# arduino_Uno_Rev3-02-TH.net
KiCad netlist of a schematic drawn in EAGLE
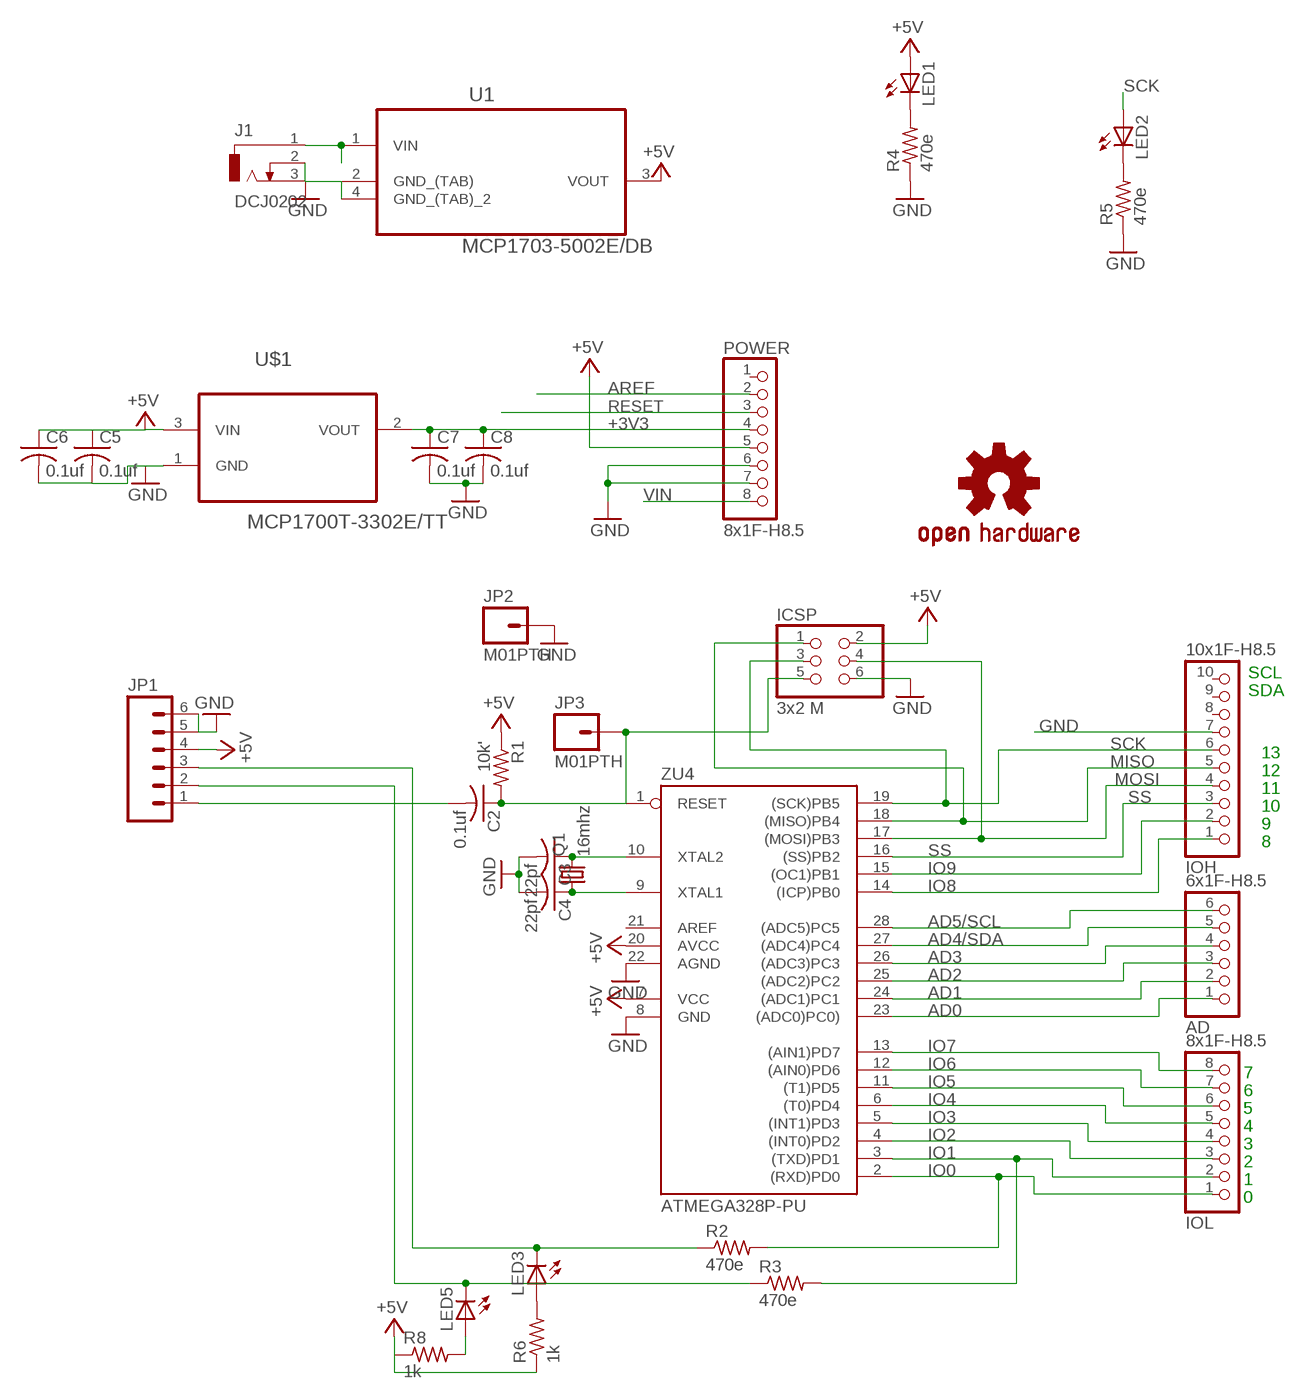
[diagram p0: schematic, sheet 1]

(export (version "E")
  (design (tool "Eeschema 10.0.6"))
  (components
    (comp (ref "AD")
      (value "6x1F-H8.5")
      (footprint "eagle-import:1X06")
      (libsource (lib "eagle-import") (part "PINHD-1X6"))
    )
    (comp (ref "C2")
      (value "0.1uf")
      (footprint "eagle-import:C0603")
      (libsource (lib "eagle-import") (part "C-USC0603"))
    )
    (comp (ref "C3")
      (value "22pf")
      (footprint "eagle-import:C1206")
      (libsource (lib "eagle-import") (part "C-USC1206"))
    )
    (comp (ref "C4")
      (value "22pf")
      (footprint "eagle-import:C1206")
      (libsource (lib "eagle-import") (part "C-USC1206"))
    )
    (comp (ref "C5")
      (value "0.1uf")
      (footprint "eagle-import:C0603")
      (libsource (lib "eagle-import") (part "C-USC0603"))
    )
    (comp (ref "C6")
      (value "0.1uf")
      (footprint "eagle-import:C0603")
      (libsource (lib "eagle-import") (part "C-USC0603"))
    )
    (comp (ref "C7")
      (value "0.1uf")
      (footprint "eagle-import:C0603")
      (libsource (lib "eagle-import") (part "C-USC0603"))
    )
    (comp (ref "C8")
      (value "0.1uf")
      (footprint "eagle-import:C0603")
      (libsource (lib "eagle-import") (part "C-USC0603"))
    )
    (comp (ref "ICSP")
      (value "3x2 M")
      (footprint "eagle-import:2X03")
      (libsource (lib "eagle-import") (part "PINHD-2X3"))
    )
    (comp (ref "IOH")
      (value "10x1F-H8.5")
      (footprint "eagle-import:1X10")
      (libsource (lib "eagle-import") (part "PINHD-1X10_ARD"))
    )
    (comp (ref "IOL")
      (value "8x1F-H8.5")
      (footprint "eagle-import:1X08")
      (libsource (lib "eagle-import") (part "PINHD-1X8"))
    )
    (comp (ref "J1")
      (value "DCJ0202")
      (footprint "eagle-import:DCJ0202")
      (libsource (lib "eagle-import") (part "DCJ0202"))
    )
    (comp (ref "JP1")
      (value "M06LONGPADS")
      (footprint "eagle-import:1X06_LONGPADS")
      (libsource (lib "eagle-import") (part "M06LONGPADS"))
    )
    (comp (ref "JP2")
      (value "M01PTH")
      (footprint "eagle-import:1X01")
      (libsource (lib "eagle-import") (part "M01PTH"))
    )
    (comp (ref "JP3")
      (value "M01PTH")
      (footprint "eagle-import:1X01")
      (libsource (lib "eagle-import") (part "M01PTH"))
    )
    (comp (ref "LED1")
      (value "LED3MM")
      (footprint "eagle-import:LED3MM")
      (libsource (lib "eagle-import") (part "LED3MM"))
    )
    (comp (ref "LED2")
      (value "LED3MM")
      (footprint "eagle-import:LED3MM")
      (libsource (lib "eagle-import") (part "LED3MM"))
    )
    (comp (ref "LED3")
      (value "LED3MM")
      (footprint "eagle-import:LED3MM")
      (libsource (lib "eagle-import") (part "LED3MM"))
    )
    (comp (ref "LED5")
      (value "LED3MM")
      (footprint "eagle-import:LED3MM")
      (libsource (lib "eagle-import") (part "LED3MM"))
    )
    (comp (ref "LOGO1")
      (value "OSHW-LOGOL")
      (footprint "eagle-import:OSHW-LOGO-L")
      (libsource (lib "eagle-import") (part "OSHW-LOGOL"))
    )
    (comp (ref "POWER")
      (value "8x1F-H8.5")
      (footprint "eagle-import:1X08")
      (libsource (lib "eagle-import") (part "PINHD-1X8"))
    )
    (comp (ref "Q1")
      (value "16mhz")
      (footprint "eagle-import:HC49_S")
      (libsource (lib "eagle-import") (part "CRYSTALHC49S"))
    )
    (comp (ref "R1")
      (value "10k'")
      (footprint "eagle-import:R0603")
      (libsource (lib "eagle-import") (part "R-US_R0603"))
    )
    (comp (ref "R2")
      (value "470e")
      (footprint "eagle-import:R0603")
      (libsource (lib "eagle-import") (part "R-US_R0603"))
    )
    (comp (ref "R3")
      (value "470e")
      (footprint "eagle-import:R0603")
      (libsource (lib "eagle-import") (part "R-US_R0603"))
    )
    (comp (ref "R4")
      (value "470e")
      (footprint "eagle-import:R0603")
      (libsource (lib "eagle-import") (part "R-US_R0603"))
    )
    (comp (ref "R5")
      (value "470e")
      (footprint "eagle-import:R0603")
      (libsource (lib "eagle-import") (part "R-US_R0603"))
    )
    (comp (ref "R6")
      (value "1k")
      (footprint "eagle-import:R0603")
      (libsource (lib "eagle-import") (part "R-US_R0603"))
    )
    (comp (ref "R8")
      (value "1k")
      (footprint "eagle-import:R0603")
      (libsource (lib "eagle-import") (part "R-US_R0603"))
    )
    (comp (ref "U$1")
      (value "MCP1700T-3302E/TT")
      (footprint "eagle-import:SOT95P237X112-3N")
      (libsource (lib "eagle-import") (part "MCP1700T-3302E/TT"))
    )
    (comp (ref "U1")
      (value "MCP1703-5002E/DB")
      (footprint "eagle-import:SOT230P700X180-4N")
      (libsource (lib "eagle-import") (part "MCP1703-5002E/DB"))
    )
    (comp (ref "ZU4")
      (value "ATMEGA328P-PU")
      (footprint "eagle-import:DIL28-3")
      (libsource (lib "eagle-import") (part "ATMEGA328P-PU"))
    )
  )
  (nets
    (net (code "1") (name "+5V") (class "Default")
      (node (ref "C5") (pin "1") (pinfunction "1_1") (pintype "passive"))
      (node (ref "C6") (pin "1") (pinfunction "1_1") (pintype "passive"))
      (node (ref "ICSP") (pin "2") (pinfunction "2_2") (pintype "passive"))
      (node (ref "JP1") (pin "4") (pinfunction "4_4") (pintype "passive"))
      (node (ref "LED1") (pin "A") (pinfunction "A_A") (pintype "passive"))
      (node (ref "POWER") (pin "5") (pinfunction "5_5") (pintype "passive"))
      (node (ref "R1") (pin "1") (pinfunction "1_1") (pintype "passive"))
      (node (ref "R6") (pin "1") (pinfunction "1_1") (pintype "passive"))
      (node (ref "R8") (pin "1") (pinfunction "1_1") (pintype "passive"))
      (node (ref "U$1") (pin "3") (pinfunction "VIN_3") (pintype "input"))
      (node (ref "U1") (pin "3") (pinfunction "VOUT_3") (pintype "output"))
      (node (ref "ZU4") (pin "20") (pinfunction "AVCC_20") (pintype "power_in"))
      (node (ref "ZU4") (pin "7") (pinfunction "VCC_7") (pintype "power_in"))
    )
    (net (code "2") (name "/+3V3") (class "Default")
      (node (ref "C7") (pin "1") (pinfunction "1_1") (pintype "passive"))
      (node (ref "C8") (pin "1") (pinfunction "1_1") (pintype "passive"))
      (node (ref "POWER") (pin "4") (pinfunction "4_4") (pintype "passive"))
      (node (ref "U$1") (pin "2") (pinfunction "VOUT_2") (pintype "output"))
    )
    (net (code "3") (name "/AD0") (class "Default")
      (node (ref "AD") (pin "1") (pinfunction "1_1") (pintype "passive"))
      (node (ref "ZU4") (pin "23") (pinfunction "(ADC0)PC0)_23") (pintype "bidirectional"))
    )
    (net (code "4") (name "/AD1") (class "Default")
      (node (ref "AD") (pin "2") (pinfunction "2_2") (pintype "passive"))
      (node (ref "ZU4") (pin "24") (pinfunction "(ADC1)PC1_24") (pintype "bidirectional"))
    )
    (net (code "5") (name "/AD2") (class "Default")
      (node (ref "AD") (pin "3") (pinfunction "3_3") (pintype "passive"))
      (node (ref "ZU4") (pin "25") (pinfunction "(ADC2)PC2_25") (pintype "bidirectional"))
    )
    (net (code "6") (name "/AD3") (class "Default")
      (node (ref "AD") (pin "4") (pinfunction "4_4") (pintype "passive"))
      (node (ref "ZU4") (pin "26") (pinfunction "(ADC3)PC3_26") (pintype "bidirectional"))
    )
    (net (code "7") (name "/AD4{slash}SDA") (class "Default")
      (node (ref "AD") (pin "5") (pinfunction "5_5") (pintype "passive"))
      (node (ref "ZU4") (pin "27") (pinfunction "(ADC4)PC4_27") (pintype "bidirectional"))
    )
    (net (code "8") (name "/AD5{slash}SCL") (class "Default")
      (node (ref "AD") (pin "6") (pinfunction "6_6") (pintype "passive"))
      (node (ref "ZU4") (pin "28") (pinfunction "(ADC5)PC5_28") (pintype "bidirectional"))
    )
    (net (code "9") (name "/AREF") (class "Default")
      (node (ref "POWER") (pin "2") (pinfunction "2_2") (pintype "passive"))
    )
    (net (code "10") (name "/IO0") (class "Default")
      (node (ref "IOL") (pin "1") (pinfunction "1_1") (pintype "passive"))
      (node (ref "R2") (pin "2") (pinfunction "2_2") (pintype "passive"))
      (node (ref "ZU4") (pin "2") (pinfunction "(RXD)PD0_2") (pintype "bidirectional"))
    )
    (net (code "11") (name "/IO1") (class "Default")
      (node (ref "IOL") (pin "2") (pinfunction "2_2") (pintype "passive"))
      (node (ref "R3") (pin "2") (pinfunction "2_2") (pintype "passive"))
      (node (ref "ZU4") (pin "3") (pinfunction "(TXD)PD1_3") (pintype "bidirectional"))
    )
    (net (code "12") (name "/IO2") (class "Default")
      (node (ref "IOL") (pin "3") (pinfunction "3_3") (pintype "passive"))
      (node (ref "ZU4") (pin "4") (pinfunction "(INT0)PD2_4") (pintype "bidirectional"))
    )
    (net (code "13") (name "/IO3") (class "Default")
      (node (ref "IOL") (pin "4") (pinfunction "4_4") (pintype "passive"))
      (node (ref "ZU4") (pin "5") (pinfunction "(INT1)PD3_5") (pintype "bidirectional"))
    )
    (net (code "14") (name "/IO4") (class "Default")
      (node (ref "IOL") (pin "5") (pinfunction "5_5") (pintype "passive"))
      (node (ref "ZU4") (pin "6") (pinfunction "(T0)PD4_6") (pintype "bidirectional"))
    )
    (net (code "15") (name "/IO5") (class "Default")
      (node (ref "IOL") (pin "6") (pinfunction "6_6") (pintype "passive"))
      (node (ref "ZU4") (pin "11") (pinfunction "(T1)PD5_11") (pintype "bidirectional"))
    )
    (net (code "16") (name "/IO6") (class "Default")
      (node (ref "IOL") (pin "7") (pinfunction "7_7") (pintype "passive"))
      (node (ref "ZU4") (pin "12") (pinfunction "(AIN0)PD6_12") (pintype "bidirectional"))
    )
    (net (code "17") (name "/IO7") (class "Default")
      (node (ref "IOL") (pin "8") (pinfunction "8_8") (pintype "passive"))
      (node (ref "ZU4") (pin "13") (pinfunction "(AIN1)PD7_13") (pintype "bidirectional"))
    )
    (net (code "18") (name "/IO8") (class "Default")
      (node (ref "IOH") (pin "1") (pinfunction "1_1") (pintype "passive"))
      (node (ref "ZU4") (pin "14") (pinfunction "(ICP)PB0_14") (pintype "bidirectional"))
    )
    (net (code "19") (name "/IO9") (class "Default")
      (node (ref "IOH") (pin "2") (pinfunction "2_2") (pintype "passive"))
      (node (ref "ZU4") (pin "15") (pinfunction "(OC1)PB1_15") (pintype "bidirectional"))
    )
    (net (code "20") (name "/MISO") (class "Default")
      (node (ref "ICSP") (pin "1") (pinfunction "1_1") (pintype "passive"))
      (node (ref "IOH") (pin "5") (pinfunction "5_5") (pintype "passive"))
      (node (ref "ZU4") (pin "18") (pinfunction "(MISO)PB4_18") (pintype "bidirectional"))
    )
    (net (code "21") (name "/MOSI") (class "Default")
      (node (ref "ICSP") (pin "4") (pinfunction "4_4") (pintype "passive"))
      (node (ref "IOH") (pin "4") (pinfunction "4_4") (pintype "passive"))
      (node (ref "ZU4") (pin "17") (pinfunction "(MOSI)PB3_17") (pintype "bidirectional"))
    )
    (net (code "22") (name "/RESET") (class "Default")
      (node (ref "C2") (pin "1") (pinfunction "1_1") (pintype "passive"))
      (node (ref "ICSP") (pin "5") (pinfunction "5_5") (pintype "passive"))
      (node (ref "JP3") (pin "1") (pinfunction "1_1") (pintype "passive"))
      (node (ref "POWER") (pin "3") (pinfunction "3_3") (pintype "passive"))
      (node (ref "R1") (pin "2") (pinfunction "2_2") (pintype "passive"))
      (node (ref "ZU4") (pin "1") (pinfunction "RESET_1") (pintype "input"))
    )
    (net (code "23") (name "/SCK") (class "Default")
      (node (ref "ICSP") (pin "3") (pinfunction "3_3") (pintype "passive"))
      (node (ref "IOH") (pin "6") (pinfunction "6_6") (pintype "passive"))
      (node (ref "LED2") (pin "A") (pinfunction "A_A") (pintype "passive"))
      (node (ref "ZU4") (pin "19") (pinfunction "(SCK)PB5_19") (pintype "bidirectional"))
    )
    (net (code "24") (name "/SS") (class "Default")
      (node (ref "IOH") (pin "3") (pinfunction "3_3") (pintype "passive"))
      (node (ref "ZU4") (pin "16") (pinfunction "(SS)PB2_16") (pintype "bidirectional"))
    )
    (net (code "25") (name "/VIN") (class "Default")
      (node (ref "J1") (pin "1") (pinfunction "1_1") (pintype "passive"))
      (node (ref "POWER") (pin "8") (pinfunction "8_8") (pintype "passive"))
      (node (ref "U1") (pin "1") (pinfunction "VIN_1") (pintype "input"))
    )
    (net (code "26") (name "GND") (class "Default")
      (node (ref "C3") (pin "2") (pinfunction "2_2") (pintype "passive"))
      (node (ref "C4") (pin "2") (pinfunction "2_2") (pintype "passive"))
      (node (ref "C5") (pin "2") (pinfunction "2_2") (pintype "passive"))
      (node (ref "C6") (pin "2") (pinfunction "2_2") (pintype "passive"))
      (node (ref "C7") (pin "2") (pinfunction "2_2") (pintype "passive"))
      (node (ref "C8") (pin "2") (pinfunction "2_2") (pintype "passive"))
      (node (ref "ICSP") (pin "6") (pinfunction "6_6") (pintype "passive"))
      (node (ref "IOH") (pin "7") (pinfunction "7_7") (pintype "passive"))
      (node (ref "J1") (pin "2") (pinfunction "2_2") (pintype "passive"))
      (node (ref "J1") (pin "3") (pinfunction "3_3") (pintype "passive"))
      (node (ref "JP1") (pin "5") (pinfunction "5_5") (pintype "passive"))
      (node (ref "JP1") (pin "6") (pinfunction "6_6") (pintype "passive"))
      (node (ref "JP2") (pin "1") (pinfunction "1_1") (pintype "passive"))
      (node (ref "POWER") (pin "6") (pinfunction "6_6") (pintype "passive"))
      (node (ref "POWER") (pin "7") (pinfunction "7_7") (pintype "passive"))
      (node (ref "R4") (pin "1") (pinfunction "1_1") (pintype "passive"))
      (node (ref "R5") (pin "1") (pinfunction "1_1") (pintype "passive"))
      (node (ref "U$1") (pin "1") (pinfunction "GND_1") (pintype "passive"))
      (node (ref "U1") (pin "2") (pinfunction "GND_(TAB)_2") (pintype "passive"))
      (node (ref "U1") (pin "4") (pinfunction "GND_(TAB)_2_4") (pintype "passive"))
      (node (ref "ZU4") (pin "22") (pinfunction "AGND_22") (pintype "power_in"))
      (node (ref "ZU4") (pin "8") (pinfunction "GND_8") (pintype "power_in"))
    )
    (net (code "27") (name "Net-(C2-Pad2)") (class "Default")
      (node (ref "C2") (pin "2") (pinfunction "2_2") (pintype "passive"))
      (node (ref "JP1") (pin "1") (pinfunction "1_1") (pintype "passive"))
    )
    (net (code "28") (name "Net-(LED1-C)") (class "Default")
      (node (ref "LED1") (pin "K") (pinfunction "C_K") (pintype "passive"))
      (node (ref "R4") (pin "2") (pinfunction "2_2") (pintype "passive"))
    )
    (net (code "29") (name "Net-(LED2-C)") (class "Default")
      (node (ref "LED2") (pin "K") (pinfunction "C_K") (pintype "passive"))
      (node (ref "R5") (pin "2") (pinfunction "2_2") (pintype "passive"))
    )
    (net (code "30") (name "Net-(LED3-C)") (class "Default")
      (node (ref "JP1") (pin "3") (pinfunction "3_3") (pintype "passive"))
      (node (ref "LED3") (pin "K") (pinfunction "C_K") (pintype "passive"))
      (node (ref "R2") (pin "1") (pinfunction "1_1") (pintype "passive"))
    )
    (net (code "31") (name "Net-(LED3-PadA)") (class "Default")
      (node (ref "LED3") (pin "A") (pinfunction "A_A") (pintype "passive"))
      (node (ref "R6") (pin "2") (pinfunction "2_2") (pintype "passive"))
    )
    (net (code "32") (name "Net-(LED5-C)") (class "Default")
      (node (ref "JP1") (pin "2") (pinfunction "2_2") (pintype "passive"))
      (node (ref "LED5") (pin "K") (pinfunction "C_K") (pintype "passive"))
      (node (ref "R3") (pin "1") (pinfunction "1_1") (pintype "passive"))
    )
    (net (code "33") (name "Net-(LED5-PadA)") (class "Default")
      (node (ref "LED5") (pin "A") (pinfunction "A_A") (pintype "passive"))
      (node (ref "R8") (pin "2") (pinfunction "2_2") (pintype "passive"))
    )
    (net (code "34") (name "Net-(ZU4-XTAL1)") (class "Default")
      (node (ref "C4") (pin "1") (pinfunction "1_1") (pintype "passive"))
      (node (ref "Q1") (pin "1") (pinfunction "1_1") (pintype "passive"))
      (node (ref "ZU4") (pin "9") (pinfunction "XTAL1_9") (pintype "bidirectional"))
    )
    (net (code "35") (name "Net-(ZU4-XTAL2)") (class "Default")
      (node (ref "C3") (pin "1") (pinfunction "1_1") (pintype "passive"))
      (node (ref "Q1") (pin "2") (pinfunction "2_2") (pintype "passive"))
      (node (ref "ZU4") (pin "10") (pinfunction "XTAL2_10") (pintype "bidirectional"))
    )
    (net (code "36") (name "unconnected-(IOH-Pad8)") (class "Default")
      (node (ref "IOH") (pin "8") (pinfunction "8_8") (pintype "passive"))
    )
    (net (code "37") (name "unconnected-(IOH-Pad9)") (class "Default")
      (node (ref "IOH") (pin "9") (pinfunction "9_9") (pintype "passive"))
    )
    (net (code "38") (name "unconnected-(IOH-Pad10)") (class "Default")
      (node (ref "IOH") (pin "10") (pinfunction "10_10") (pintype "passive"))
    )
    (net (code "39") (name "unconnected-(POWER-Pad1)") (class "Default")
      (node (ref "POWER") (pin "1") (pinfunction "1_1") (pintype "passive"))
    )
    (net (code "40") (name "unconnected-(ZU4-AREF-Pad21)") (class "Default")
      (node (ref "ZU4") (pin "21") (pinfunction "AREF_21") (pintype "passive"))
    )
  )
)
